# mech_thonkiconn_breakout.net
KiCad netlist of a schematic drawn in EAGLE
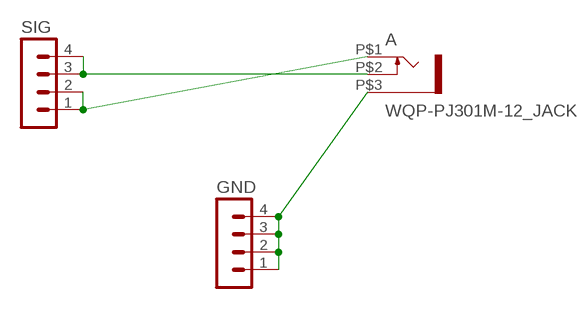
[diagram p0: schematic, sheet 1]

(export (version "E")
  (design (tool "Eeschema 10.0.6"))
  (components
    (comp (ref "A")
      (value "WQP-PJ301M-12_JACK")
      (footprint "eagle-import:WQP-PJ301M-12_JACK")
      (libsource (lib "eagle-import") (part "WQP-PJ301M-12_JACK"))
    )
    (comp (ref "GND")
      (value "MA04-1")
      (footprint "eagle-import:MA04-1")
      (libsource (lib "eagle-import") (part "MA04-1"))
    )
    (comp (ref "SIG")
      (value "MA04-1")
      (footprint "eagle-import:MA04-1")
      (libsource (lib "eagle-import") (part "MA04-1"))
    )
  )
  (nets
    (net (code "1") (name "Net-(A-1)") (class "Default")
      (node (ref "A") (pin "P$3") (pinfunction "1_P$3") (pintype "passive"))
      (node (ref "GND") (pin "1") (pinfunction "1_1") (pintype "passive"))
      (node (ref "GND") (pin "2") (pinfunction "2_2") (pintype "passive"))
      (node (ref "GND") (pin "3") (pinfunction "3_3") (pintype "passive"))
      (node (ref "GND") (pin "4") (pinfunction "4_4") (pintype "passive"))
    )
    (net (code "2") (name "Net-(A-2)") (class "Default")
      (node (ref "A") (pin "P$1") (pinfunction "2_P$1") (pintype "passive"))
      (node (ref "SIG") (pin "1") (pinfunction "1_1") (pintype "passive"))
      (node (ref "SIG") (pin "2") (pinfunction "2_2") (pintype "passive"))
    )
    (net (code "3") (name "Net-(A-3)") (class "Default")
      (node (ref "A") (pin "P$2") (pinfunction "3_P$2") (pintype "passive"))
      (node (ref "SIG") (pin "3") (pinfunction "3_3") (pintype "passive"))
      (node (ref "SIG") (pin "4") (pinfunction "4_4") (pintype "passive"))
    )
  )
)
